# Power_supplies.net
KiCad netlist of a schematic drawn in Altium Designer
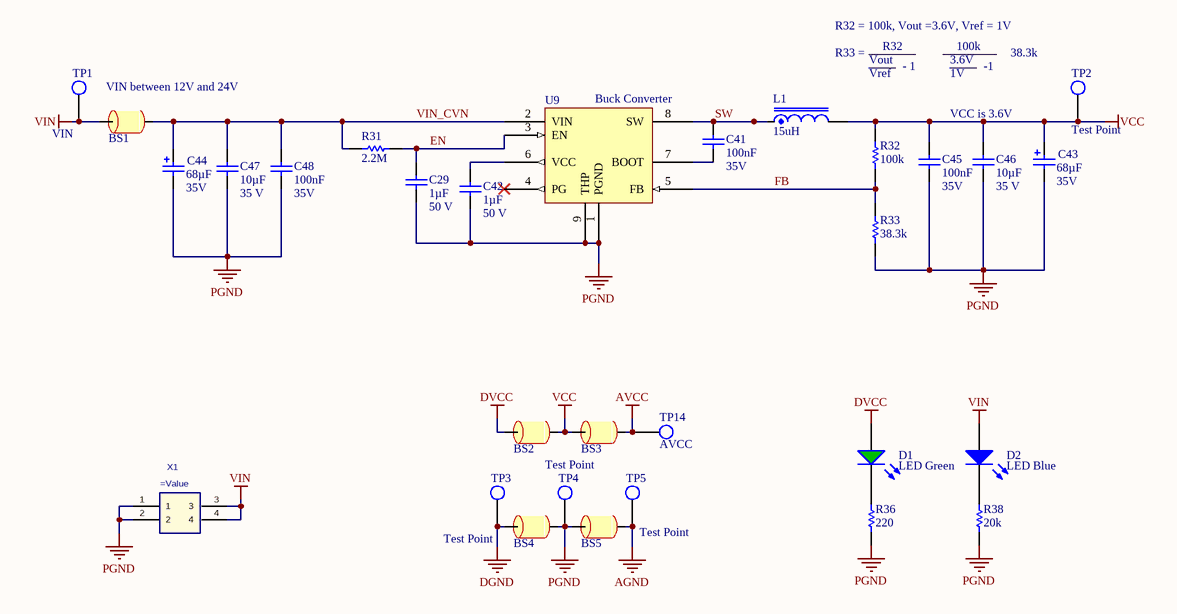
[diagram p0: Power supplies.SchDoc]

(export (version "E")
  (design (tool "Eeschema 10.0.6"))
  (components
    (comp (ref "BS1")
      (value "Ferrite bead")
      (footprint "RES_1206")
      (description "6A")
      (fields (field (name "MPN") "742792121") (field (name "MF") "Würth Elektronik"))
      (libsource (lib "Componentes_SOC") (part "Bead"))
    )
    (comp (ref "BS2")
      (value "Ferrite bead")
      (footprint "RES_1206")
      (description "6A")
      (fields (field (name "MPN") "742792121") (field (name "MF") "Würth Elektronik"))
      (libsource (lib "Componentes_SOC") (part "Bead"))
    )
    (comp (ref "BS3")
      (value "Ferrite bead")
      (footprint "RES_1206")
      (description "6A")
      (fields (field (name "MPN") "742792121") (field (name "MF") "Würth Elektronik"))
      (libsource (lib "Componentes_SOC") (part "Bead"))
    )
    (comp (ref "BS4")
      (value "Ferrite bead")
      (footprint "RES_1206")
      (description "6A")
      (fields (field (name "MPN") "742792121") (field (name "MF") "Würth Elektronik"))
      (libsource (lib "Componentes_SOC") (part "Bead"))
    )
    (comp (ref "BS5")
      (value "Ferrite bead")
      (footprint "RES_1206")
      (description "6A")
      (fields (field (name "MPN") "742792121") (field (name "MF") "Würth Elektronik"))
      (libsource (lib "Componentes_SOC") (part "Bead"))
    )
    (comp (ref "C29")
      (value "1µF")
      (footprint "CAP_0603")
      (description "Capacitor Ceramic")
      (fields
        (field (name "MPN") "C0603C105K3RACTU")
        (field (name "VOLTAGE") "50 V")
        (field (name "MF") "KEMET")
      )
      (libsource (lib "Componentes_SOC") (part "Cap_0603"))
    )
    (comp (ref "C41")
      (value "100nF")
      (footprint "CAP_0603")
      (description "Capacitor")
      (fields
        (field (name "MPN") "C0603C104M5RACTU")
        (field (name "MF") "KEMET")
        (field (name "VOLTAGE") "35V")
        (field (name "PUBLISHER") "Altium Limited")
      )
      (libsource (lib "Componentes_SOC") (part "Cap_0603"))
    )
    (comp (ref "C42")
      (value "1µF")
      (footprint "CAP_0603")
      (description "Capacitor Ceramic")
      (fields
        (field (name "MPN") "C0603C105K3RACTU")
        (field (name "VOLTAGE") "50 V")
        (field (name "MF") "KEMET")
      )
      (libsource (lib "Componentes_SOC") (part "Cap_0603"))
    )
    (comp (ref "C43")
      (value "68µF")
      (footprint "WCAP-ATG8_6.3x11")
      (description "WCAP-ATG8 THT Aluminum Electrolytic Capacitors, D6.3mm x L11mm, 68uF, +/-20%, 35VDC")
      (fields
        (field (name "PART NUMBER") "860010573006")
        (field (name "TOLERANCE") "+/-20%")
        (field (name "VOLTAGE") "35V")
        (field (name "PUBLISHER") "Wurth Elektronik")
      )
      (libsource (lib "Componentes_SOC") (part "860010573006"))
    )
    (comp (ref "C44")
      (value "68µF")
      (footprint "WCAP-ATG8_6.3x11")
      (description "WCAP-ATG8 THT Aluminum Electrolytic Capacitors, D6.3mm x L11mm, 68uF, +/-20%, 35VDC")
      (fields
        (field (name "PART NUMBER") "860010573006")
        (field (name "TOLERANCE") "+/-20%")
        (field (name "VOLTAGE") "35V")
        (field (name "PUBLISHER") "Wurth Elektronik")
      )
      (libsource (lib "Componentes_SOC") (part "860010573006"))
    )
    (comp (ref "C45")
      (value "100nF")
      (footprint "CAP_0603")
      (description "Capacitor")
      (fields
        (field (name "MPN") "C0603C104M5RACTU")
        (field (name "MF") "KEMET")
        (field (name "VOLTAGE") "35V")
        (field (name "PUBLISHER") "Altium Limited")
      )
      (libsource (lib "Componentes_SOC") (part "Cap_0603"))
    )
    (comp (ref "C46")
      (value "10µF")
      (footprint "RES_1206")
      (description "Capacitor")
      (fields
        (field (name "MPN") "GRM319R6YA106KA12D")
        (field (name "VOLTAGE") "35 V")
        (field (name "TOLERANCE") "10%")
      )
      (libsource (lib "Componentes_SOC") (part "Cap_1206"))
    )
    (comp (ref "C47")
      (value "10µF")
      (footprint "RES_1206")
      (description "Capacitor")
      (fields
        (field (name "MPN") "GRM319R6YA106KA12D")
        (field (name "VOLTAGE") "35 V")
        (field (name "TOLERANCE") "10%")
      )
      (libsource (lib "Componentes_SOC") (part "Cap_1206"))
    )
    (comp (ref "C48")
      (value "100nF")
      (footprint "CAP_0603")
      (description "Capacitor")
      (fields
        (field (name "MPN") "C0603C104M5RACTU")
        (field (name "MF") "KEMET")
        (field (name "VOLTAGE") "35V")
        (field (name "PUBLISHER") "Altium Limited")
      )
      (libsource (lib "Componentes_SOC") (part "Cap_0603"))
    )
    (comp (ref "D1")
      (value "LED Green")
      (footprint "WL-SMCW_0603")
      (description "Standard LEDs - SMD 0603 green")
      (fields
        (field (name "MANUFACTURER PART NUMBER") "UZgen_LED_0603_Green")
        (field (name "MANUFACTURER") "UZgen")
        (field (name "CREATED FROM") "UZgenTool")
      )
      (libsource (lib "user") (part "LED_Green"))
    )
    (comp (ref "D2")
      (value "LED Blue")
      (footprint "WL-SMCW_0603")
      (description "Standard LEDs - SMD 0603 blue")
      (fields
        (field (name "MANUFACTURER PART NUMBER") "UZgen_LED_0603_Blue")
        (field (name "MANUFACTURER") "UZgen")
        (field (name "CREATED FROM") "UZgenTool")
      )
      (libsource (lib "user") (part "LED_Blue"))
    )
    (comp (ref "L1")
      (value "15uH")
      (footprint "SMT_inductor_1050_Performance")
      (description "SMT power Inductor, 15uH, 40m DRC")
      (fields (field (name "MF") "Murata") (field (name "LCSC PART NUMBER") "C6818993"))
      (libsource (lib "Componentes_SOC") (part "B82464G4154M"))
    )
    (comp (ref "R31")
      (value "2.2M")
      (footprint "RES_0603")
      (fields
        (field (name "MF") "Yageo")
        (field (name "MPN") "RC0603FR-072M2L")
        (field (name "TOLERANCE") "1%")
        (field (name "PUBLISHER") "Altium Limited")
      )
      (libsource (lib "Componentes_SOC") (part "Res0603"))
    )
    (comp (ref "R32")
      (value "100k")
      (footprint "RES_0603")
      (fields
        (field (name "MF") "Yageo")
        (field (name "MPN") "RC0603FR-07100KL")
        (field (name "TOLERANCE") "1%")
        (field (name "PUBLISHER") "Altium Limited")
      )
      (libsource (lib "Componentes_SOC") (part "Res0603"))
    )
    (comp (ref "R33")
      (value "38.3k")
      (footprint "RES_0603")
      (fields (field (name "TOLERANCE") "1%") (field (name "PUBLISHER") "Altium Limited"))
      (libsource (lib "Componentes_SOC") (part "Res0603"))
    )
    (comp (ref "R36")
      (value "220")
      (footprint "RES_0603")
      (fields
        (field (name "MPN") "RC0603JR-07220RL")
        (field (name "TOLERANCE") "1%")
        (field (name "PUBLISHER") "Altium Limited")
      )
      (libsource (lib "Componentes_SOC") (part "Res0603"))
    )
    (comp (ref "R38")
      (value "20k")
      (footprint "RES_0603")
      (fields
        (field (name "MPN") "RC0603FR-07330RL")
        (field (name "MF") "Yageo")
        (field (name "TOLERANCE") "1%")
        (field (name "PUBLISHER") "Altium Limited")
      )
      (libsource (lib "Componentes_SOC") (part "Res0603"))
    )
    (comp (ref "TP1")
      (value "VIN")
      (footprint "TP_1.6mm")
      (description "1.6mm Test Point Keystone")
      (fields
        (field (name "MF") "Keystone Electronics")
        (field (name "MPN") "5006")
        (field (name "CREATED") "2020_04_Kreppel")
      )
      (libsource (lib "Componentes_SOC") (part "TP"))
    )
    (comp (ref "TP2")
      (value "Test Point")
      (footprint "TP_1.6mm")
      (description "1.6mm Test Point Keystone")
      (fields
        (field (name "MF") "Keystone Electronics")
        (field (name "MPN") "5006")
        (field (name "CREATED") "2020_04_Kreppel")
      )
      (libsource (lib "Componentes_SOC") (part "TP"))
    )
    (comp (ref "TP3")
      (value "Test Point")
      (footprint "TP_1.6mm")
      (description "1.6mm Test Point Keystone")
      (fields
        (field (name "MF") "Keystone Electronics")
        (field (name "MPN") "5006")
        (field (name "CREATED") "2020_04_Kreppel")
      )
      (libsource (lib "Componentes_SOC") (part "TP"))
    )
    (comp (ref "TP4")
      (value "Test Point")
      (footprint "TP_1.6mm")
      (description "1.6mm Test Point Keystone")
      (fields
        (field (name "MF") "Keystone Electronics")
        (field (name "MPN") "5006")
        (field (name "CREATED") "2020_04_Kreppel")
      )
      (libsource (lib "Componentes_SOC") (part "TP"))
    )
    (comp (ref "TP5")
      (value "Test Point")
      (footprint "TP_1.6mm")
      (description "1.6mm Test Point Keystone")
      (fields
        (field (name "MF") "Keystone Electronics")
        (field (name "MPN") "5006")
        (field (name "CREATED") "2020_04_Kreppel")
      )
      (libsource (lib "Componentes_SOC") (part "TP"))
    )
    (comp (ref "TP14")
      (value "AVCC")
      (footprint "TP_1.6mm")
      (description "1.6mm Test Point Keystone")
      (fields
        (field (name "MF") "Keystone Electronics")
        (field (name "MPN") "5006")
        (field (name "CREATED") "2020_04_Kreppel")
      )
      (libsource (lib "Componentes_SOC") (part "TP"))
    )
    (comp (ref "U9")
      (value "Buck Converter")
      (footprint "SOIC127P600X170_HS-9N")
      (description "3.8V to 36V, 2A synchronous step-down converter")
      (fields
        (field (name "MF") "Texas Instruments")
        (field (name "MPN") "LMR33620ADDA")
        (field (name "CREATED") "4/20 Kreppel")
      )
      (libsource (lib "Componentes_SOC") (part "LMR33620A"))
    )
    (comp (ref "X1")
      (value "~")
      (footprint "IPL1-102-01-L-D-K")
      (description "2.54mm Double Row Terminal Assembly, Right-Angled")
      (fields
        (field (name "MF") "SAMTEC")
        (field (name "MPN") "IPL1-102-01-L-D-K")
        (field (name "CREATED") "2018_05_02_AGeiger")
      )
      (libsource (lib "Componentes_SOC") (part "IPL1-102-XX-X-D-X"))
    )
  )
  (nets
    (net (code "1") (name "/EN") (class "Default")
      (node (ref "C29") (pin "1") (pinfunction "1_1") (pintype "passive"))
      (node (ref "R31") (pin "1") (pinfunction "1_1") (pintype "passive"))
      (node (ref "U9") (pin "3") (pinfunction "EN_3") (pintype "input"))
    )
    (net (code "2") (name "/FB") (class "Default")
      (node (ref "R32") (pin "1") (pinfunction "1_1") (pintype "passive"))
      (node (ref "R33") (pin "2") (pinfunction "2_2") (pintype "passive"))
      (node (ref "U9") (pin "5") (pinfunction "FB_5") (pintype "input"))
    )
    (net (code "3") (name "/SW") (class "Default")
      (node (ref "C41") (pin "1") (pinfunction "1_1") (pintype "passive"))
      (node (ref "L1") (pin "1") (pinfunction "1_1") (pintype "passive"))
      (node (ref "U9") (pin "8") (pinfunction "SW_8") (pintype "power_in"))
    )
    (net (code "4") (name "/VIN_CVN") (class "Default")
      (node (ref "BS1") (pin "2") (pintype "passive"))
      (node (ref "C44") (pin "2") (pinfunction "P_2") (pintype "passive"))
      (node (ref "C47") (pin "1") (pinfunction "1_1") (pintype "passive"))
      (node (ref "C48") (pin "1") (pinfunction "1_1") (pintype "passive"))
      (node (ref "R31") (pin "2") (pinfunction "2_2") (pintype "passive"))
      (node (ref "U9") (pin "2") (pinfunction "VIN_2") (pintype "power_in"))
    )
    (net (code "5") (name "AGND") (class "Default")
      (node (ref "BS5") (pin "2") (pintype "passive"))
      (node (ref "TP5") (pin "1") (pinfunction "1_1") (pintype "passive"))
    )
    (net (code "6") (name "AVCC") (class "Default")
      (node (ref "BS3") (pin "2") (pintype "passive"))
      (node (ref "TP14") (pin "1") (pinfunction "1_1") (pintype "passive"))
    )
    (net (code "7") (name "DGND") (class "Default")
      (node (ref "BS4") (pin "1") (pintype "passive"))
      (node (ref "TP3") (pin "1") (pinfunction "1_1") (pintype "passive"))
    )
    (net (code "8") (name "DVCC") (class "Default")
      (node (ref "BS2") (pin "1") (pintype "passive"))
      (node (ref "D1") (pin "2") (pinfunction "A_2") (pintype "passive"))
    )
    (net (code "9") (name "Net-(D1-K)") (class "Default")
      (node (ref "D1") (pin "1") (pinfunction "K_1") (pintype "passive"))
      (node (ref "R36") (pin "2") (pinfunction "2_2") (pintype "passive"))
    )
    (net (code "10") (name "Net-(D2-K)") (class "Default")
      (node (ref "D2") (pin "1") (pinfunction "K_1") (pintype "passive"))
      (node (ref "R38") (pin "1") (pinfunction "1_1") (pintype "passive"))
    )
    (net (code "11") (name "Net-(U9-BOOT)") (class "Default")
      (node (ref "C41") (pin "2") (pinfunction "2_2") (pintype "passive"))
      (node (ref "U9") (pin "7") (pinfunction "BOOT_7") (pintype "power_in"))
    )
    (net (code "12") (name "Net-(U9-VCC)") (class "Default")
      (node (ref "C42") (pin "1") (pinfunction "1_1") (pintype "passive"))
      (node (ref "U9") (pin "6") (pinfunction "VCC_6") (pintype "output"))
    )
    (net (code "13") (name "PGND") (class "Default")
      (node (ref "BS4") (pin "2") (pintype "passive"))
      (node (ref "BS5") (pin "1") (pintype "passive"))
      (node (ref "C29") (pin "2") (pinfunction "2_2") (pintype "passive"))
      (node (ref "C42") (pin "2") (pinfunction "2_2") (pintype "passive"))
      (node (ref "C43") (pin "1") (pinfunction "N_1") (pintype "passive"))
      (node (ref "C44") (pin "1") (pinfunction "N_1") (pintype "passive"))
      (node (ref "C45") (pin "2") (pinfunction "2_2") (pintype "passive"))
      (node (ref "C46") (pin "2") (pinfunction "2_2") (pintype "passive"))
      (node (ref "C47") (pin "2") (pinfunction "2_2") (pintype "passive"))
      (node (ref "C48") (pin "2") (pinfunction "2_2") (pintype "passive"))
      (node (ref "R33") (pin "1") (pinfunction "1_1") (pintype "passive"))
      (node (ref "R36") (pin "1") (pinfunction "1_1") (pintype "passive"))
      (node (ref "R38") (pin "2") (pinfunction "2_2") (pintype "passive"))
      (node (ref "TP4") (pin "1") (pinfunction "1_1") (pintype "passive"))
      (node (ref "U9") (pin "1") (pinfunction "PGND_1") (pintype "power_in"))
      (node (ref "U9") (pin "9") (pinfunction "THP_9") (pintype "passive"))
      (node (ref "X1") (pin "1") (pinfunction "1_1") (pintype "passive"))
      (node (ref "X1") (pin "2") (pinfunction "2_2") (pintype "passive"))
    )
    (net (code "14") (name "VCC") (class "Default")
      (node (ref "BS2") (pin "2") (pintype "passive"))
      (node (ref "BS3") (pin "1") (pintype "passive"))
      (node (ref "C43") (pin "2") (pinfunction "P_2") (pintype "passive"))
      (node (ref "C45") (pin "1") (pinfunction "1_1") (pintype "passive"))
      (node (ref "C46") (pin "1") (pinfunction "1_1") (pintype "passive"))
      (node (ref "L1") (pin "2") (pinfunction "2_2") (pintype "passive"))
      (node (ref "R32") (pin "2") (pinfunction "2_2") (pintype "passive"))
      (node (ref "TP2") (pin "1") (pinfunction "1_1") (pintype "passive"))
    )
    (net (code "15") (name "VIN") (class "Default")
      (node (ref "BS1") (pin "1") (pintype "passive"))
      (node (ref "D2") (pin "2") (pinfunction "A_2") (pintype "passive"))
      (node (ref "TP1") (pin "1") (pinfunction "1_1") (pintype "passive"))
      (node (ref "X1") (pin "3") (pinfunction "3_3") (pintype "passive"))
      (node (ref "X1") (pin "4") (pinfunction "4_4") (pintype "passive"))
    )
    (net (code "16") (name "unconnected-(U9-PG-Pad4)") (class "Default")
      (node (ref "U9") (pin "4") (pinfunction "PG_4") (pintype "output+no_connect"))
    )
  )
)
